# hdl.net
KiCad netlist of a schematic drawn in EAGLE
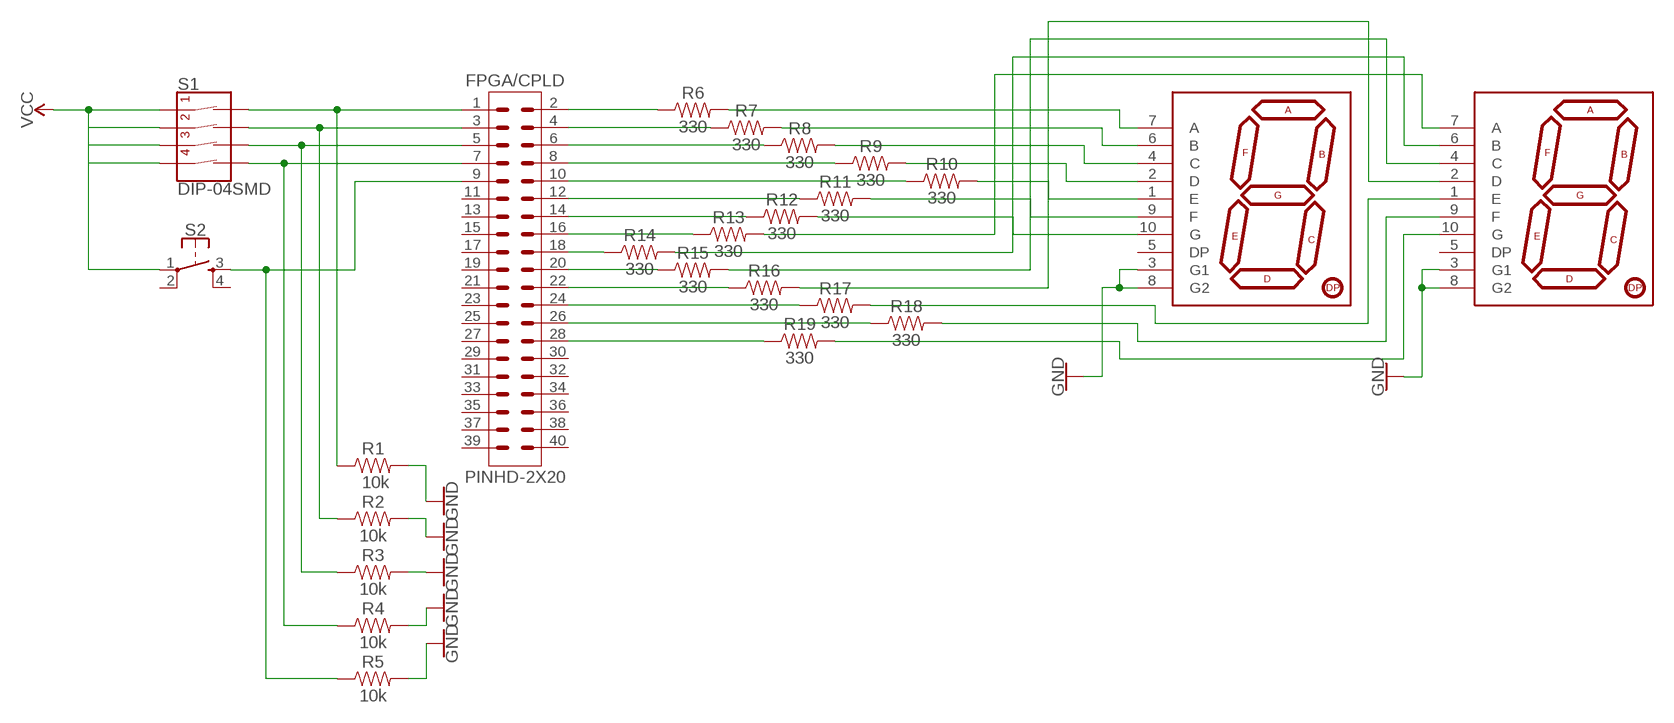
[diagram p0: schematic, sheet 1]

(export (version "E")
  (design (tool "Eeschema 10.0.6"))
  (components
    (comp (ref "FPGA/CPLD")
      (value "PINHD-2X20")
      (footprint "eagle-import:2X20")
      (libsource (lib "eagle-import") (part "PINHD-2X20"))
    )
    (comp (ref "R1")
      (value "10k")
      (footprint "eagle-import:0402")
      (libsource (lib "eagle-import") (part "RESISTOR0402"))
    )
    (comp (ref "R2")
      (value "10k")
      (footprint "eagle-import:0402")
      (libsource (lib "eagle-import") (part "RESISTOR0402"))
    )
    (comp (ref "R3")
      (value "10k")
      (footprint "eagle-import:0402")
      (libsource (lib "eagle-import") (part "RESISTOR0402"))
    )
    (comp (ref "R4")
      (value "10k")
      (footprint "eagle-import:0402")
      (libsource (lib "eagle-import") (part "RESISTOR0402"))
    )
    (comp (ref "R5")
      (value "10k")
      (footprint "eagle-import:0402")
      (libsource (lib "eagle-import") (part "RESISTOR0402"))
    )
    (comp (ref "R6")
      (value "330")
      (footprint "eagle-import:0402")
      (libsource (lib "eagle-import") (part "RESISTOR0402"))
    )
    (comp (ref "R7")
      (value "330")
      (footprint "eagle-import:0402")
      (libsource (lib "eagle-import") (part "RESISTOR0402"))
    )
    (comp (ref "R8")
      (value "330")
      (footprint "eagle-import:0402")
      (libsource (lib "eagle-import") (part "RESISTOR0402"))
    )
    (comp (ref "R9")
      (value "330")
      (footprint "eagle-import:0402")
      (libsource (lib "eagle-import") (part "RESISTOR0402"))
    )
    (comp (ref "R10")
      (value "330")
      (footprint "eagle-import:0402")
      (libsource (lib "eagle-import") (part "RESISTOR0402"))
    )
    (comp (ref "R11")
      (value "330")
      (footprint "eagle-import:0402")
      (libsource (lib "eagle-import") (part "RESISTOR0402"))
    )
    (comp (ref "R12")
      (value "330")
      (footprint "eagle-import:0402")
      (libsource (lib "eagle-import") (part "RESISTOR0402"))
    )
    (comp (ref "R13")
      (value "330")
      (footprint "eagle-import:0402")
      (libsource (lib "eagle-import") (part "RESISTOR0402"))
    )
    (comp (ref "R14")
      (value "330")
      (footprint "eagle-import:0402")
      (libsource (lib "eagle-import") (part "RESISTOR0402"))
    )
    (comp (ref "R15")
      (value "330")
      (footprint "eagle-import:0402")
      (libsource (lib "eagle-import") (part "RESISTOR0402"))
    )
    (comp (ref "R16")
      (value "330")
      (footprint "eagle-import:0402")
      (libsource (lib "eagle-import") (part "RESISTOR0402"))
    )
    (comp (ref "R17")
      (value "330")
      (footprint "eagle-import:0402")
      (libsource (lib "eagle-import") (part "RESISTOR0402"))
    )
    (comp (ref "R18")
      (value "330")
      (footprint "eagle-import:0402")
      (libsource (lib "eagle-import") (part "RESISTOR0402"))
    )
    (comp (ref "R19")
      (value "330")
      (footprint "eagle-import:0402")
      (libsource (lib "eagle-import") (part "RESISTOR0402"))
    )
    (comp (ref "S1")
      (value "DIP-04SMD")
      (footprint "eagle-import:DIPSWITCH-04-SMD")
      (libsource (lib "eagle-import") (part "DIP-04SMD"))
    )
    (comp (ref "S2")
      (value "MOMENTARY-SWITCH-SPST-2-SMD-4.6X2.8MM")
      (footprint "eagle-import:TACTILE_SWITCH_SMD_4.6X2.8MM")
      (libsource (lib "eagle-import") (part "MOMENTARY-SWITCH-SPST-2-SMD-4.6X2.8MM"))
    )
    (comp (ref "U$1")
      (value "YSD-1601AR4B-8")
      (footprint "eagle-import:7-SEGMENT-1_PTH-EZ")
      (libsource (lib "eagle-import") (part "7-SEGMENT-1DIGIT-1INCH-RED-EZ"))
    )
    (comp (ref "U$2")
      (value "YSD-1601AR4B-8")
      (footprint "eagle-import:7-SEGMENT-1_PTH-EZ")
      (libsource (lib "eagle-import") (part "7-SEGMENT-1DIGIT-1INCH-RED-EZ"))
    )
  )
  (nets
    (net (code "1") (name "GND") (class "Default")
      (node (ref "R1") (pin "2") (pinfunction "2_2") (pintype "passive"))
      (node (ref "R2") (pin "2") (pinfunction "2_2") (pintype "passive"))
      (node (ref "R3") (pin "2") (pinfunction "2_2") (pintype "passive"))
      (node (ref "R4") (pin "2") (pinfunction "2_2") (pintype "passive"))
      (node (ref "R5") (pin "2") (pinfunction "2_2") (pintype "passive"))
      (node (ref "U$1") (pin "3") (pinfunction "G1_3") (pintype "bidirectional"))
      (node (ref "U$1") (pin "8") (pinfunction "G2_8") (pintype "bidirectional"))
      (node (ref "U$2") (pin "3") (pinfunction "G1_3") (pintype "bidirectional"))
      (node (ref "U$2") (pin "8") (pinfunction "G2_8") (pintype "bidirectional"))
    )
    (net (code "2") (name "Net-(FPGA/CPLD-Pad2)") (class "Default")
      (node (ref "FPGA/CPLD") (pin "2") (pinfunction "2_2") (pintype "passive"))
      (node (ref "R6") (pin "1") (pinfunction "1_1") (pintype "passive"))
    )
    (net (code "3") (name "Net-(FPGA/CPLD-Pad4)") (class "Default")
      (node (ref "FPGA/CPLD") (pin "4") (pinfunction "4_4") (pintype "passive"))
      (node (ref "R7") (pin "1") (pinfunction "1_1") (pintype "passive"))
    )
    (net (code "4") (name "Net-(FPGA/CPLD-Pad6)") (class "Default")
      (node (ref "FPGA/CPLD") (pin "6") (pinfunction "6_6") (pintype "passive"))
      (node (ref "R8") (pin "1") (pinfunction "1_1") (pintype "passive"))
    )
    (net (code "5") (name "Net-(FPGA/CPLD-Pad8)") (class "Default")
      (node (ref "FPGA/CPLD") (pin "8") (pinfunction "8_8") (pintype "passive"))
      (node (ref "R9") (pin "1") (pinfunction "1_1") (pintype "passive"))
    )
    (net (code "6") (name "Net-(FPGA/CPLD-Pad9)") (class "Default")
      (node (ref "FPGA/CPLD") (pin "9") (pinfunction "9_9") (pintype "passive"))
      (node (ref "R5") (pin "1") (pinfunction "1_1") (pintype "passive"))
      (node (ref "S2") (pin "3") (pinfunction "3_3") (pintype "passive"))
    )
    (net (code "7") (name "Net-(FPGA/CPLD-Pad10)") (class "Default")
      (node (ref "FPGA/CPLD") (pin "10") (pinfunction "10_10") (pintype "passive"))
      (node (ref "R10") (pin "1") (pinfunction "1_1") (pintype "passive"))
    )
    (net (code "8") (name "Net-(FPGA/CPLD-Pad12)") (class "Default")
      (node (ref "FPGA/CPLD") (pin "12") (pinfunction "12_12") (pintype "passive"))
      (node (ref "R11") (pin "1") (pinfunction "1_1") (pintype "passive"))
    )
    (net (code "9") (name "Net-(FPGA/CPLD-Pad14)") (class "Default")
      (node (ref "FPGA/CPLD") (pin "14") (pinfunction "14_14") (pintype "passive"))
      (node (ref "R12") (pin "1") (pinfunction "1_1") (pintype "passive"))
    )
    (net (code "10") (name "Net-(FPGA/CPLD-Pad16)") (class "Default")
      (node (ref "FPGA/CPLD") (pin "16") (pinfunction "16_16") (pintype "passive"))
      (node (ref "R13") (pin "1") (pinfunction "1_1") (pintype "passive"))
    )
    (net (code "11") (name "Net-(FPGA/CPLD-Pad18)") (class "Default")
      (node (ref "FPGA/CPLD") (pin "18") (pinfunction "18_18") (pintype "passive"))
      (node (ref "R14") (pin "1") (pinfunction "1_1") (pintype "passive"))
    )
    (net (code "12") (name "Net-(FPGA/CPLD-Pad20)") (class "Default")
      (node (ref "FPGA/CPLD") (pin "20") (pinfunction "20_20") (pintype "passive"))
      (node (ref "R15") (pin "1") (pinfunction "1_1") (pintype "passive"))
    )
    (net (code "13") (name "Net-(FPGA/CPLD-Pad22)") (class "Default")
      (node (ref "FPGA/CPLD") (pin "22") (pinfunction "22_22") (pintype "passive"))
      (node (ref "R16") (pin "1") (pinfunction "1_1") (pintype "passive"))
    )
    (net (code "14") (name "Net-(FPGA/CPLD-Pad24)") (class "Default")
      (node (ref "FPGA/CPLD") (pin "24") (pinfunction "24_24") (pintype "passive"))
      (node (ref "R17") (pin "1") (pinfunction "1_1") (pintype "passive"))
    )
    (net (code "15") (name "Net-(FPGA/CPLD-Pad26)") (class "Default")
      (node (ref "FPGA/CPLD") (pin "26") (pinfunction "26_26") (pintype "passive"))
      (node (ref "R18") (pin "1") (pinfunction "1_1") (pintype "passive"))
    )
    (net (code "16") (name "Net-(FPGA/CPLD-Pad28)") (class "Default")
      (node (ref "FPGA/CPLD") (pin "28") (pinfunction "28_28") (pintype "passive"))
      (node (ref "R19") (pin "1") (pinfunction "1_1") (pintype "passive"))
    )
    (net (code "17") (name "Net-(S1-1A)") (class "Default")
      (node (ref "FPGA/CPLD") (pin "1") (pinfunction "1_1") (pintype "passive"))
      (node (ref "R1") (pin "1") (pinfunction "1_1") (pintype "passive"))
      (node (ref "S1") (pin "1") (pinfunction "1A_1") (pintype "bidirectional"))
    )
    (net (code "18") (name "Net-(S1-2A)") (class "Default")
      (node (ref "FPGA/CPLD") (pin "3") (pinfunction "3_3") (pintype "passive"))
      (node (ref "R2") (pin "1") (pinfunction "1_1") (pintype "passive"))
      (node (ref "S1") (pin "2") (pinfunction "2A_2") (pintype "bidirectional"))
    )
    (net (code "19") (name "Net-(S1-3A)") (class "Default")
      (node (ref "FPGA/CPLD") (pin "5") (pinfunction "5_5") (pintype "passive"))
      (node (ref "R3") (pin "1") (pinfunction "1_1") (pintype "passive"))
      (node (ref "S1") (pin "3") (pinfunction "3A_3") (pintype "bidirectional"))
    )
    (net (code "20") (name "Net-(S1-4A)") (class "Default")
      (node (ref "FPGA/CPLD") (pin "7") (pinfunction "7_7") (pintype "passive"))
      (node (ref "R4") (pin "1") (pinfunction "1_1") (pintype "passive"))
      (node (ref "S1") (pin "4") (pinfunction "4A_4") (pintype "bidirectional"))
    )
    (net (code "21") (name "Net-(U$1-A)") (class "Default")
      (node (ref "R6") (pin "2") (pinfunction "2_2") (pintype "passive"))
      (node (ref "U$1") (pin "7") (pinfunction "A_7") (pintype "bidirectional"))
    )
    (net (code "22") (name "Net-(U$1-B)") (class "Default")
      (node (ref "R7") (pin "2") (pinfunction "2_2") (pintype "passive"))
      (node (ref "U$1") (pin "6") (pinfunction "B_6") (pintype "bidirectional"))
    )
    (net (code "23") (name "Net-(U$1-C)") (class "Default")
      (node (ref "R8") (pin "2") (pinfunction "2_2") (pintype "passive"))
      (node (ref "U$1") (pin "4") (pinfunction "C_4") (pintype "bidirectional"))
    )
    (net (code "24") (name "Net-(U$1-D)") (class "Default")
      (node (ref "R9") (pin "2") (pinfunction "2_2") (pintype "passive"))
      (node (ref "U$1") (pin "2") (pinfunction "D_2") (pintype "bidirectional"))
    )
    (net (code "25") (name "Net-(U$1-E)") (class "Default")
      (node (ref "R10") (pin "2") (pinfunction "2_2") (pintype "passive"))
      (node (ref "U$1") (pin "1") (pinfunction "E_1") (pintype "bidirectional"))
    )
    (net (code "26") (name "Net-(U$1-F)") (class "Default")
      (node (ref "R11") (pin "2") (pinfunction "2_2") (pintype "passive"))
      (node (ref "U$1") (pin "9") (pinfunction "F_9") (pintype "bidirectional"))
    )
    (net (code "27") (name "Net-(U$1-G)") (class "Default")
      (node (ref "R12") (pin "2") (pinfunction "2_2") (pintype "passive"))
      (node (ref "U$1") (pin "10") (pinfunction "G_10") (pintype "bidirectional"))
    )
    (net (code "28") (name "Net-(U$2-A)") (class "Default")
      (node (ref "R13") (pin "2") (pinfunction "2_2") (pintype "passive"))
      (node (ref "U$2") (pin "7") (pinfunction "A_7") (pintype "bidirectional"))
    )
    (net (code "29") (name "Net-(U$2-B)") (class "Default")
      (node (ref "R14") (pin "2") (pinfunction "2_2") (pintype "passive"))
      (node (ref "U$2") (pin "6") (pinfunction "B_6") (pintype "bidirectional"))
    )
    (net (code "30") (name "Net-(U$2-C)") (class "Default")
      (node (ref "R15") (pin "2") (pinfunction "2_2") (pintype "passive"))
      (node (ref "U$2") (pin "4") (pinfunction "C_4") (pintype "bidirectional"))
    )
    (net (code "31") (name "Net-(U$2-D)") (class "Default")
      (node (ref "R16") (pin "2") (pinfunction "2_2") (pintype "passive"))
      (node (ref "U$2") (pin "2") (pinfunction "D_2") (pintype "bidirectional"))
    )
    (net (code "32") (name "Net-(U$2-E)") (class "Default")
      (node (ref "R17") (pin "2") (pinfunction "2_2") (pintype "passive"))
      (node (ref "U$2") (pin "1") (pinfunction "E_1") (pintype "bidirectional"))
    )
    (net (code "33") (name "Net-(U$2-F)") (class "Default")
      (node (ref "R18") (pin "2") (pinfunction "2_2") (pintype "passive"))
      (node (ref "U$2") (pin "9") (pinfunction "F_9") (pintype "bidirectional"))
    )
    (net (code "34") (name "Net-(U$2-G)") (class "Default")
      (node (ref "R19") (pin "2") (pinfunction "2_2") (pintype "passive"))
      (node (ref "U$2") (pin "10") (pinfunction "G_10") (pintype "bidirectional"))
    )
    (net (code "35") (name "VCC") (class "Default")
      (node (ref "S1") (pin "5") (pinfunction "4B_5") (pintype "bidirectional"))
      (node (ref "S1") (pin "6") (pinfunction "3B_6") (pintype "bidirectional"))
      (node (ref "S1") (pin "7") (pinfunction "2B_7") (pintype "bidirectional"))
      (node (ref "S1") (pin "8") (pinfunction "1B_8") (pintype "bidirectional"))
      (node (ref "S2") (pin "1") (pinfunction "1_1") (pintype "passive"))
    )
    (net (code "36") (name "unconnected-(FPGA/CPLD-Pad11)") (class "Default")
      (node (ref "FPGA/CPLD") (pin "11") (pinfunction "11_11") (pintype "passive"))
    )
    (net (code "37") (name "unconnected-(FPGA/CPLD-Pad13)") (class "Default")
      (node (ref "FPGA/CPLD") (pin "13") (pinfunction "13_13") (pintype "passive"))
    )
    (net (code "38") (name "unconnected-(FPGA/CPLD-Pad15)") (class "Default")
      (node (ref "FPGA/CPLD") (pin "15") (pinfunction "15_15") (pintype "passive"))
    )
    (net (code "39") (name "unconnected-(FPGA/CPLD-Pad17)") (class "Default")
      (node (ref "FPGA/CPLD") (pin "17") (pinfunction "17_17") (pintype "passive"))
    )
    (net (code "40") (name "unconnected-(FPGA/CPLD-Pad19)") (class "Default")
      (node (ref "FPGA/CPLD") (pin "19") (pinfunction "19_19") (pintype "passive"))
    )
    (net (code "41") (name "unconnected-(FPGA/CPLD-Pad21)") (class "Default")
      (node (ref "FPGA/CPLD") (pin "21") (pinfunction "21_21") (pintype "passive"))
    )
    (net (code "42") (name "unconnected-(FPGA/CPLD-Pad23)") (class "Default")
      (node (ref "FPGA/CPLD") (pin "23") (pinfunction "23_23") (pintype "passive"))
    )
    (net (code "43") (name "unconnected-(FPGA/CPLD-Pad25)") (class "Default")
      (node (ref "FPGA/CPLD") (pin "25") (pinfunction "25_25") (pintype "passive"))
    )
    (net (code "44") (name "unconnected-(FPGA/CPLD-Pad27)") (class "Default")
      (node (ref "FPGA/CPLD") (pin "27") (pinfunction "27_27") (pintype "passive"))
    )
    (net (code "45") (name "unconnected-(FPGA/CPLD-Pad29)") (class "Default")
      (node (ref "FPGA/CPLD") (pin "29") (pinfunction "29_29") (pintype "passive"))
    )
    (net (code "46") (name "unconnected-(FPGA/CPLD-Pad30)") (class "Default")
      (node (ref "FPGA/CPLD") (pin "30") (pinfunction "30_30") (pintype "passive"))
    )
    (net (code "47") (name "unconnected-(FPGA/CPLD-Pad31)") (class "Default")
      (node (ref "FPGA/CPLD") (pin "31") (pinfunction "31_31") (pintype "passive"))
    )
    (net (code "48") (name "unconnected-(FPGA/CPLD-Pad32)") (class "Default")
      (node (ref "FPGA/CPLD") (pin "32") (pinfunction "32_32") (pintype "passive"))
    )
    (net (code "49") (name "unconnected-(FPGA/CPLD-Pad33)") (class "Default")
      (node (ref "FPGA/CPLD") (pin "33") (pinfunction "33_33") (pintype "passive"))
    )
    (net (code "50") (name "unconnected-(FPGA/CPLD-Pad34)") (class "Default")
      (node (ref "FPGA/CPLD") (pin "34") (pinfunction "34_34") (pintype "passive"))
    )
    (net (code "51") (name "unconnected-(FPGA/CPLD-Pad35)") (class "Default")
      (node (ref "FPGA/CPLD") (pin "35") (pinfunction "35_35") (pintype "passive"))
    )
    (net (code "52") (name "unconnected-(FPGA/CPLD-Pad36)") (class "Default")
      (node (ref "FPGA/CPLD") (pin "36") (pinfunction "36_36") (pintype "passive"))
    )
    (net (code "53") (name "unconnected-(FPGA/CPLD-Pad37)") (class "Default")
      (node (ref "FPGA/CPLD") (pin "37") (pinfunction "37_37") (pintype "passive"))
    )
    (net (code "54") (name "unconnected-(FPGA/CPLD-Pad38)") (class "Default")
      (node (ref "FPGA/CPLD") (pin "38") (pinfunction "38_38") (pintype "passive"))
    )
    (net (code "55") (name "unconnected-(FPGA/CPLD-Pad39)") (class "Default")
      (node (ref "FPGA/CPLD") (pin "39") (pinfunction "39_39") (pintype "passive"))
    )
    (net (code "56") (name "unconnected-(FPGA/CPLD-Pad40)") (class "Default")
      (node (ref "FPGA/CPLD") (pin "40") (pinfunction "40_40") (pintype "passive"))
    )
    (net (code "57") (name "unconnected-(S2-Pad2)") (class "Default")
      (node (ref "S2") (pin "2") (pinfunction "2_2") (pintype "passive"))
    )
    (net (code "58") (name "unconnected-(S2-Pad4)") (class "Default")
      (node (ref "S2") (pin "4") (pinfunction "4_4") (pintype "passive"))
    )
    (net (code "59") (name "unconnected-(U$1-DP-Pad5)") (class "Default")
      (node (ref "U$1") (pin "5") (pinfunction "DP_5") (pintype "bidirectional"))
    )
    (net (code "60") (name "unconnected-(U$2-DP-Pad5)") (class "Default")
      (node (ref "U$2") (pin "5") (pinfunction "DP_5") (pintype "bidirectional"))
    )
  )
)
